# CS_IC.net
KiCad netlist of a schematic drawn in Altium Designer
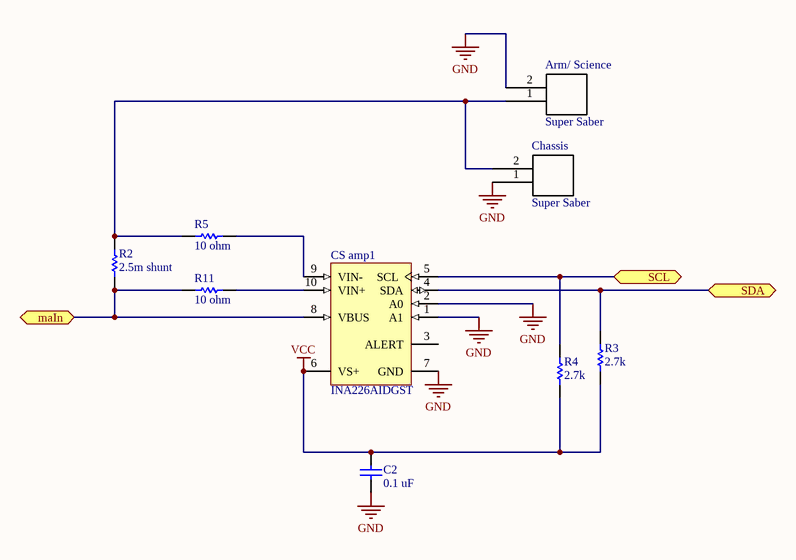
[diagram p0: CS IC.SchDoc]

(export (version "E")
  (design (tool "Eeschema 10.0.6"))
  (components
    (comp (ref "Arm/ Science")
      (value "Super Saber")
      (footprint "0431600102")
      (libsource (lib "Connector Schematic Symbols") (part "Super Saber"))
    )
    (comp (ref "C2")
      (value "0.1 uF")
      (footprint "CAPC0805(2012)130_N")
      (description "CAP 390pF 200V ±5% 0805 (2012 Metric) Thickness 1.3mm SMD")
      (fields (field (name "TOLERANCE") "Â±5%"))
      (libsource (lib "Altium Content Vault") (part "CAP"))
    )
    (comp (ref "Chassis")
      (value "Super Saber")
      (footprint "0431600102")
      (libsource (lib "Connector Schematic Symbols") (part "Super Saber"))
    )
    (comp (ref "CS amp1")
      (value "INA226AIDGST")
      (footprint "DGS0010A_N")
      (libsource (lib "Altium Content Vault") (part "TI-INA226DGS10"))
    )
    (comp (ref "R2")
      (value "2.5m shunt")
      (footprint "RESC0805(2012)_N")
      (description "SR32L500FE66")
      (fields (field (name "TOLERANCE") "1 %") (field (name "POWER") "0.125 W"))
      (libsource (lib "Altium Content Vault") (part "RES"))
    )
    (comp (ref "R3")
      (value "2.7k")
      (footprint "RESC0805(2012)_N")
      (description "160R 0.125W 1% 0805 (2012 Metric)  SMD")
      (fields (field (name "TOLERANCE") "1 %") (field (name "POWER") "0.125 W"))
      (libsource (lib "Altium Content Vault") (part "RES"))
    )
    (comp (ref "R4")
      (value "2.7k")
      (footprint "RESC0805(2012)_N")
      (description "160R 0.125W 1% 0805 (2012 Metric)  SMD")
      (fields (field (name "TOLERANCE") "1 %") (field (name "POWER") "0.125 W"))
      (libsource (lib "Altium Content Vault") (part "RES"))
    )
    (comp (ref "R5")
      (value "10 ohm")
      (footprint "RESC0805(2012)_N")
      (description "160R 0.125W 1% 0805 (2012 Metric)  SMD")
      (fields (field (name "TOLERANCE") "1 %") (field (name "POWER") "0.125 W"))
      (libsource (lib "Altium Content Vault") (part "RES"))
    )
    (comp (ref "R11")
      (value "10 ohm")
      (footprint "RESC0805(2012)_N")
      (description "160R 0.125W 1% 0805 (2012 Metric)  SMD")
      (fields (field (name "TOLERANCE") "1 %") (field (name "POWER") "0.125 W"))
      (libsource (lib "Altium Content Vault") (part "RES"))
    )
  )
  (nets
    (net (code "1") (name "/SCL") (class "Default")
      (node (ref "CS amp1") (pin "5") (pinfunction "SCL_5") (pintype "input"))
      (node (ref "R4") (pin "2") (pinfunction "2_2") (pintype "passive"))
    )
    (net (code "2") (name "/SDA") (class "Default")
      (node (ref "CS amp1") (pin "4") (pinfunction "SDA_4") (pintype "bidirectional"))
      (node (ref "R3") (pin "2") (pinfunction "2_2") (pintype "passive"))
    )
    (net (code "3") (name "/maIn") (class "Default")
      (node (ref "CS amp1") (pin "8") (pinfunction "VBUS_8") (pintype "input"))
      (node (ref "R11") (pin "2") (pinfunction "2_2") (pintype "passive"))
      (node (ref "R2") (pin "1") (pinfunction "1_1") (pintype "passive"))
    )
    (net (code "4") (name "GND") (class "Default")
      (node (ref "Arm/ Science") (pin "2") (pintype "passive"))
      (node (ref "C2") (pin "1") (pinfunction "1_1") (pintype "passive"))
      (node (ref "CS amp1") (pin "1") (pinfunction "A1_1") (pintype "input"))
      (node (ref "CS amp1") (pin "2") (pinfunction "A0_2") (pintype "input"))
      (node (ref "CS amp1") (pin "7") (pinfunction "GND_7") (pintype "power_in"))
      (node (ref "Chassis") (pin "1") (pintype "passive"))
    )
    (net (code "5") (name "Net-(Arm/ Science-Pad1)") (class "Default")
      (node (ref "Arm/ Science") (pin "1") (pintype "passive"))
      (node (ref "Chassis") (pin "2") (pintype "passive"))
      (node (ref "R2") (pin "2") (pinfunction "2_2") (pintype "passive"))
      (node (ref "R5") (pin "2") (pinfunction "2_2") (pintype "passive"))
    )
    (net (code "6") (name "Net-(CS amp1-VIN+)") (class "Default")
      (node (ref "CS amp1") (pin "10") (pinfunction "VIN+_10") (pintype "input"))
      (node (ref "R11") (pin "1") (pinfunction "1_1") (pintype "passive"))
    )
    (net (code "7") (name "Net-(CS amp1-VIN-)") (class "Default")
      (node (ref "CS amp1") (pin "9") (pinfunction "VIN-_9") (pintype "input"))
      (node (ref "R5") (pin "1") (pinfunction "1_1") (pintype "passive"))
    )
    (net (code "8") (name "VCC") (class "Default")
      (node (ref "C2") (pin "2") (pinfunction "2_2") (pintype "passive"))
      (node (ref "CS amp1") (pin "6") (pinfunction "VS+_6") (pintype "power_in"))
      (node (ref "R3") (pin "1") (pinfunction "1_1") (pintype "passive"))
      (node (ref "R4") (pin "1") (pinfunction "1_1") (pintype "passive"))
    )
    (net (code "9") (name "unconnected-(CS amp1-ALERT-Pad3)") (class "Default")
      (node (ref "CS amp1") (pin "3") (pinfunction "ALERT_3") (pintype "open_collector"))
    )
  )
)
